# LED_DriverR2.net
KiCad netlist of a schematic drawn in Altium Designer
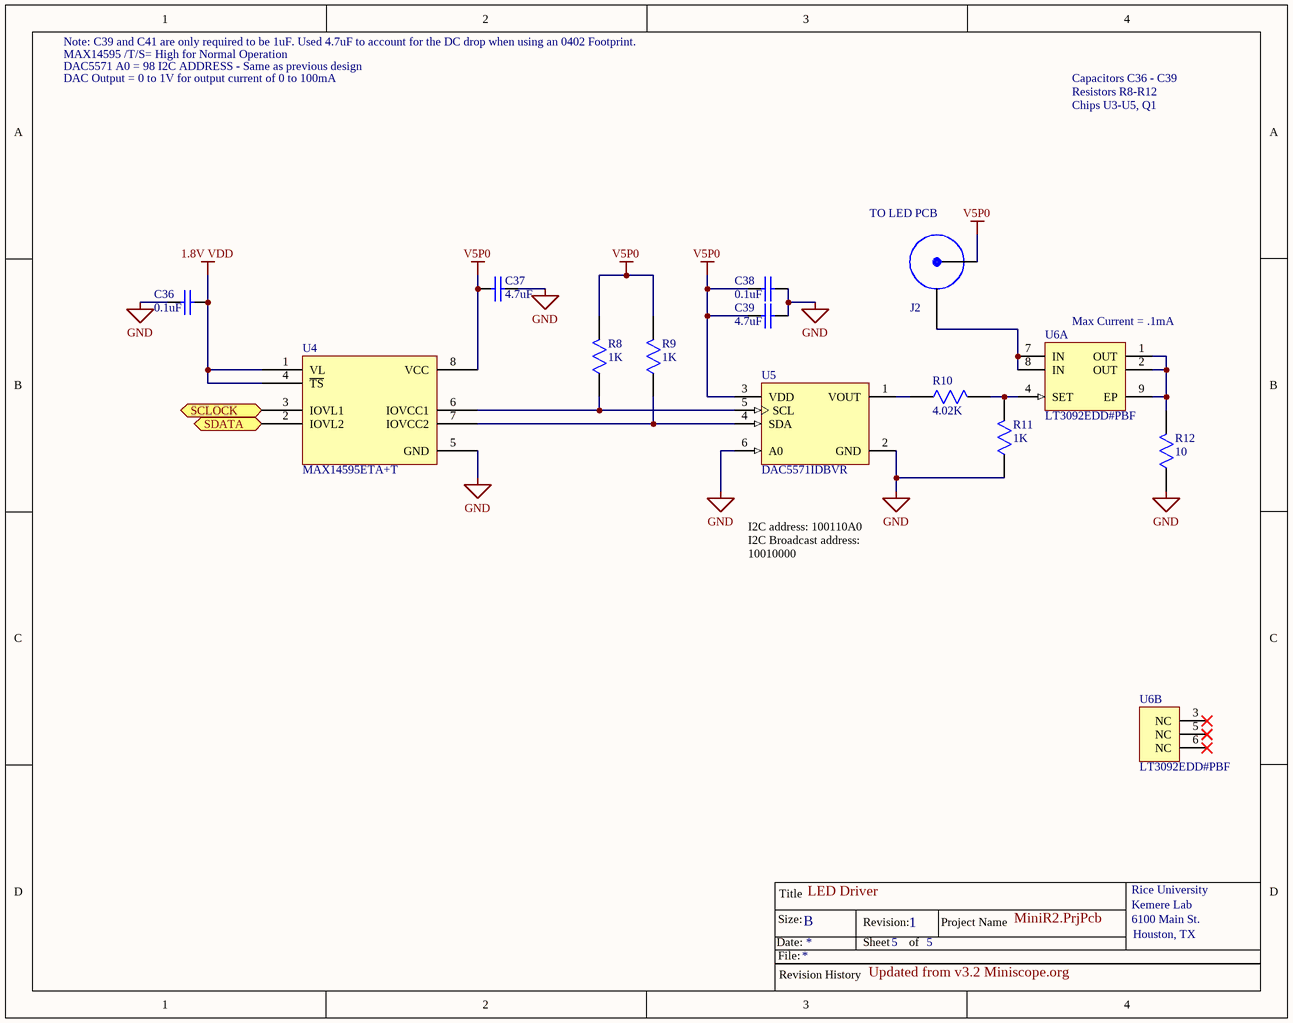
[diagram p0: LED_DriverR2.SchDoc]

(export (version "E")
  (design (tool "Eeschema 10.0.6"))
  (components
    (comp (ref "C36")
      (value "0.1uF")
      (footprint "SMD CAP 0402")
      (libsource (lib "DA_Component_Library") (part "Capacitor"))
    )
    (comp (ref "C37")
      (value "4.7uF")
      (footprint "SMD CAP 0402")
      (libsource (lib "DA_Component_Library") (part "Capacitor"))
    )
    (comp (ref "C38")
      (value "0.1uF")
      (footprint "SMD CAP 0402")
      (libsource (lib "DA_Component_Library") (part "Capacitor"))
    )
    (comp (ref "C39")
      (value "4.7uF")
      (footprint "SMD CAP 0402")
      (libsource (lib "DA_Component_Library") (part "Capacitor"))
    )
    (comp (ref "J2")
      (value "Coax Connector")
      (footprint "Coax Direct Solder ThroughHoles")
      (libsource (lib "DA_Component_Library") (part "Coax Connector"))
    )
    (comp (ref "R8")
      (value "1K")
      (footprint "SMD RES 0402")
      (libsource (lib "DA_Component_Library") (part "Resistor"))
    )
    (comp (ref "R9")
      (value "1K")
      (footprint "SMD RES 0402")
      (libsource (lib "DA_Component_Library") (part "Resistor"))
    )
    (comp (ref "R10")
      (value "4.02K")
      (footprint "SMD RES 0402")
      (libsource (lib "DA_Component_Library") (part "Resistor"))
    )
    (comp (ref "R11")
      (value "1K")
      (footprint "SMD RES 0402")
      (libsource (lib "DA_Component_Library") (part "Resistor"))
    )
    (comp (ref "R12")
      (value "10")
      (footprint "SMD RES 0402")
      (libsource (lib "DA_Component_Library") (part "Resistor"))
    )
    (comp (ref "U4")
      (value "MAX14595ETA+T")
      (footprint "8 TDFN")
      (description "Level Translator")
      (libsource (lib "Miniscope") (part "MAX14595ETA+T"))
    )
    (comp (ref "U5") (value "DAC5571IDBVR") (footprint "DBV") (libsource (lib "Miniscope") (part "DAC5571")))
    (comp (ref "U6")
      (value "LT3092EDD#PBF")
      (footprint "LT-DD-8_V")
      (fields (field (name "MANUFACTURER") "Linear Technology"))
      (libsource (lib "DA_Component_Library") (part "LT3092EDD#PBF"))
    )
  )
  (nets
    (net (code "1") (name "/SCLOCK") (class "Default")
      (node (ref "U4") (pin "3") (pinfunction "IOVL1_3") (pintype "passive"))
    )
    (net (code "2") (name "/SDATA") (class "Default")
      (node (ref "U4") (pin "2") (pinfunction "IOVL2_2") (pintype "passive"))
    )
    (net (code "3") (name "1.8V VDD") (class "Default")
      (node (ref "C36") (pin "1") (pinfunction "1_1") (pintype "passive"))
      (node (ref "U4") (pin "1") (pinfunction "VL_1") (pintype "passive"))
      (node (ref "U4") (pin "4") (pinfunction "~{TS}_4") (pintype "passive"))
    )
    (net (code "4") (name "GND") (class "Default")
      (node (ref "C36") (pin "0") (pinfunction "0_0") (pintype "passive"))
      (node (ref "C37") (pin "1") (pinfunction "1_1") (pintype "passive"))
      (node (ref "C38") (pin "1") (pinfunction "1_1") (pintype "passive"))
      (node (ref "C39") (pin "1") (pinfunction "1_1") (pintype "passive"))
      (node (ref "R11") (pin "0") (pinfunction "0_0") (pintype "passive"))
      (node (ref "R12") (pin "0") (pinfunction "0_0") (pintype "passive"))
      (node (ref "U4") (pin "5") (pinfunction "GND_5") (pintype "passive"))
      (node (ref "U5") (pin "2") (pinfunction "GND_2") (pintype "power_in"))
      (node (ref "U5") (pin "6") (pinfunction "A0_6") (pintype "input"))
    )
    (net (code "5") (name "Net-(J2-Pad1)") (class "Default")
      (node (ref "J2") (pin "1") (pinfunction "1_1") (pintype "passive"))
      (node (ref "U6") (pin "7") (pinfunction "IN_7") (pintype "power_in"))
      (node (ref "U6") (pin "8") (pinfunction "IN_8") (pintype "power_in"))
    )
    (net (code "6") (name "Net-(U4-IOVCC1)") (class "Default")
      (node (ref "R8") (pin "0") (pinfunction "0_0") (pintype "passive"))
      (node (ref "U4") (pin "6") (pinfunction "IOVCC1_6") (pintype "passive"))
      (node (ref "U5") (pin "5") (pinfunction "SCL_5") (pintype "input"))
    )
    (net (code "7") (name "Net-(U4-IOVCC2)") (class "Default")
      (node (ref "R9") (pin "0") (pinfunction "0_0") (pintype "passive"))
      (node (ref "U4") (pin "7") (pinfunction "IOVCC2_7") (pintype "passive"))
      (node (ref "U5") (pin "4") (pinfunction "SDA_4") (pintype "input"))
    )
    (net (code "8") (name "Net-(U5-VOUT)") (class "Default")
      (node (ref "R10") (pin "0") (pinfunction "0_0") (pintype "passive"))
      (node (ref "U5") (pin "1") (pinfunction "VOUT_1") (pintype "tri_state"))
    )
    (net (code "9") (name "Net-(U6A-EP)") (class "Default")
      (node (ref "R12") (pin "1") (pinfunction "1_1") (pintype "passive"))
      (node (ref "U6") (pin "1") (pinfunction "OUT_1") (pintype "power_in"))
      (node (ref "U6") (pin "2") (pinfunction "OUT_2") (pintype "power_in"))
      (node (ref "U6") (pin "9") (pinfunction "EP_9") (pintype "power_in"))
    )
    (net (code "10") (name "Net-(U6A-SET)") (class "Default")
      (node (ref "R10") (pin "1") (pinfunction "1_1") (pintype "passive"))
      (node (ref "R11") (pin "1") (pinfunction "1_1") (pintype "passive"))
      (node (ref "U6") (pin "4") (pinfunction "SET_4") (pintype "input"))
    )
    (net (code "11") (name "V5P0") (class "Default")
      (node (ref "C37") (pin "0") (pinfunction "0_0") (pintype "passive"))
      (node (ref "C38") (pin "0") (pinfunction "0_0") (pintype "passive"))
      (node (ref "C39") (pin "0") (pinfunction "0_0") (pintype "passive"))
      (node (ref "J2") (pin "0") (pinfunction "0_0") (pintype "passive"))
      (node (ref "R8") (pin "1") (pinfunction "1_1") (pintype "passive"))
      (node (ref "R9") (pin "1") (pinfunction "1_1") (pintype "passive"))
      (node (ref "U4") (pin "8") (pinfunction "VCC_8") (pintype "passive"))
      (node (ref "U5") (pin "3") (pinfunction "VDD_3") (pintype "power_in"))
    )
    (net (code "12") (name "unconnected-(U6B-NC-Pad3)") (class "Default")
      (node (ref "U6") (pin "3") (pinfunction "NC_3") (pintype "passive+no_connect"))
    )
    (net (code "13") (name "unconnected-(U6B-NC-Pad5)") (class "Default")
      (node (ref "U6") (pin "5") (pinfunction "NC_5") (pintype "passive+no_connect"))
    )
    (net (code "14") (name "unconnected-(U6B-NC-Pad6)") (class "Default")
      (node (ref "U6") (pin "6") (pinfunction "NC_6") (pintype "passive+no_connect"))
    )
  )
)
